# USB_C.net
KiCad netlist of a schematic drawn in Altium Designer
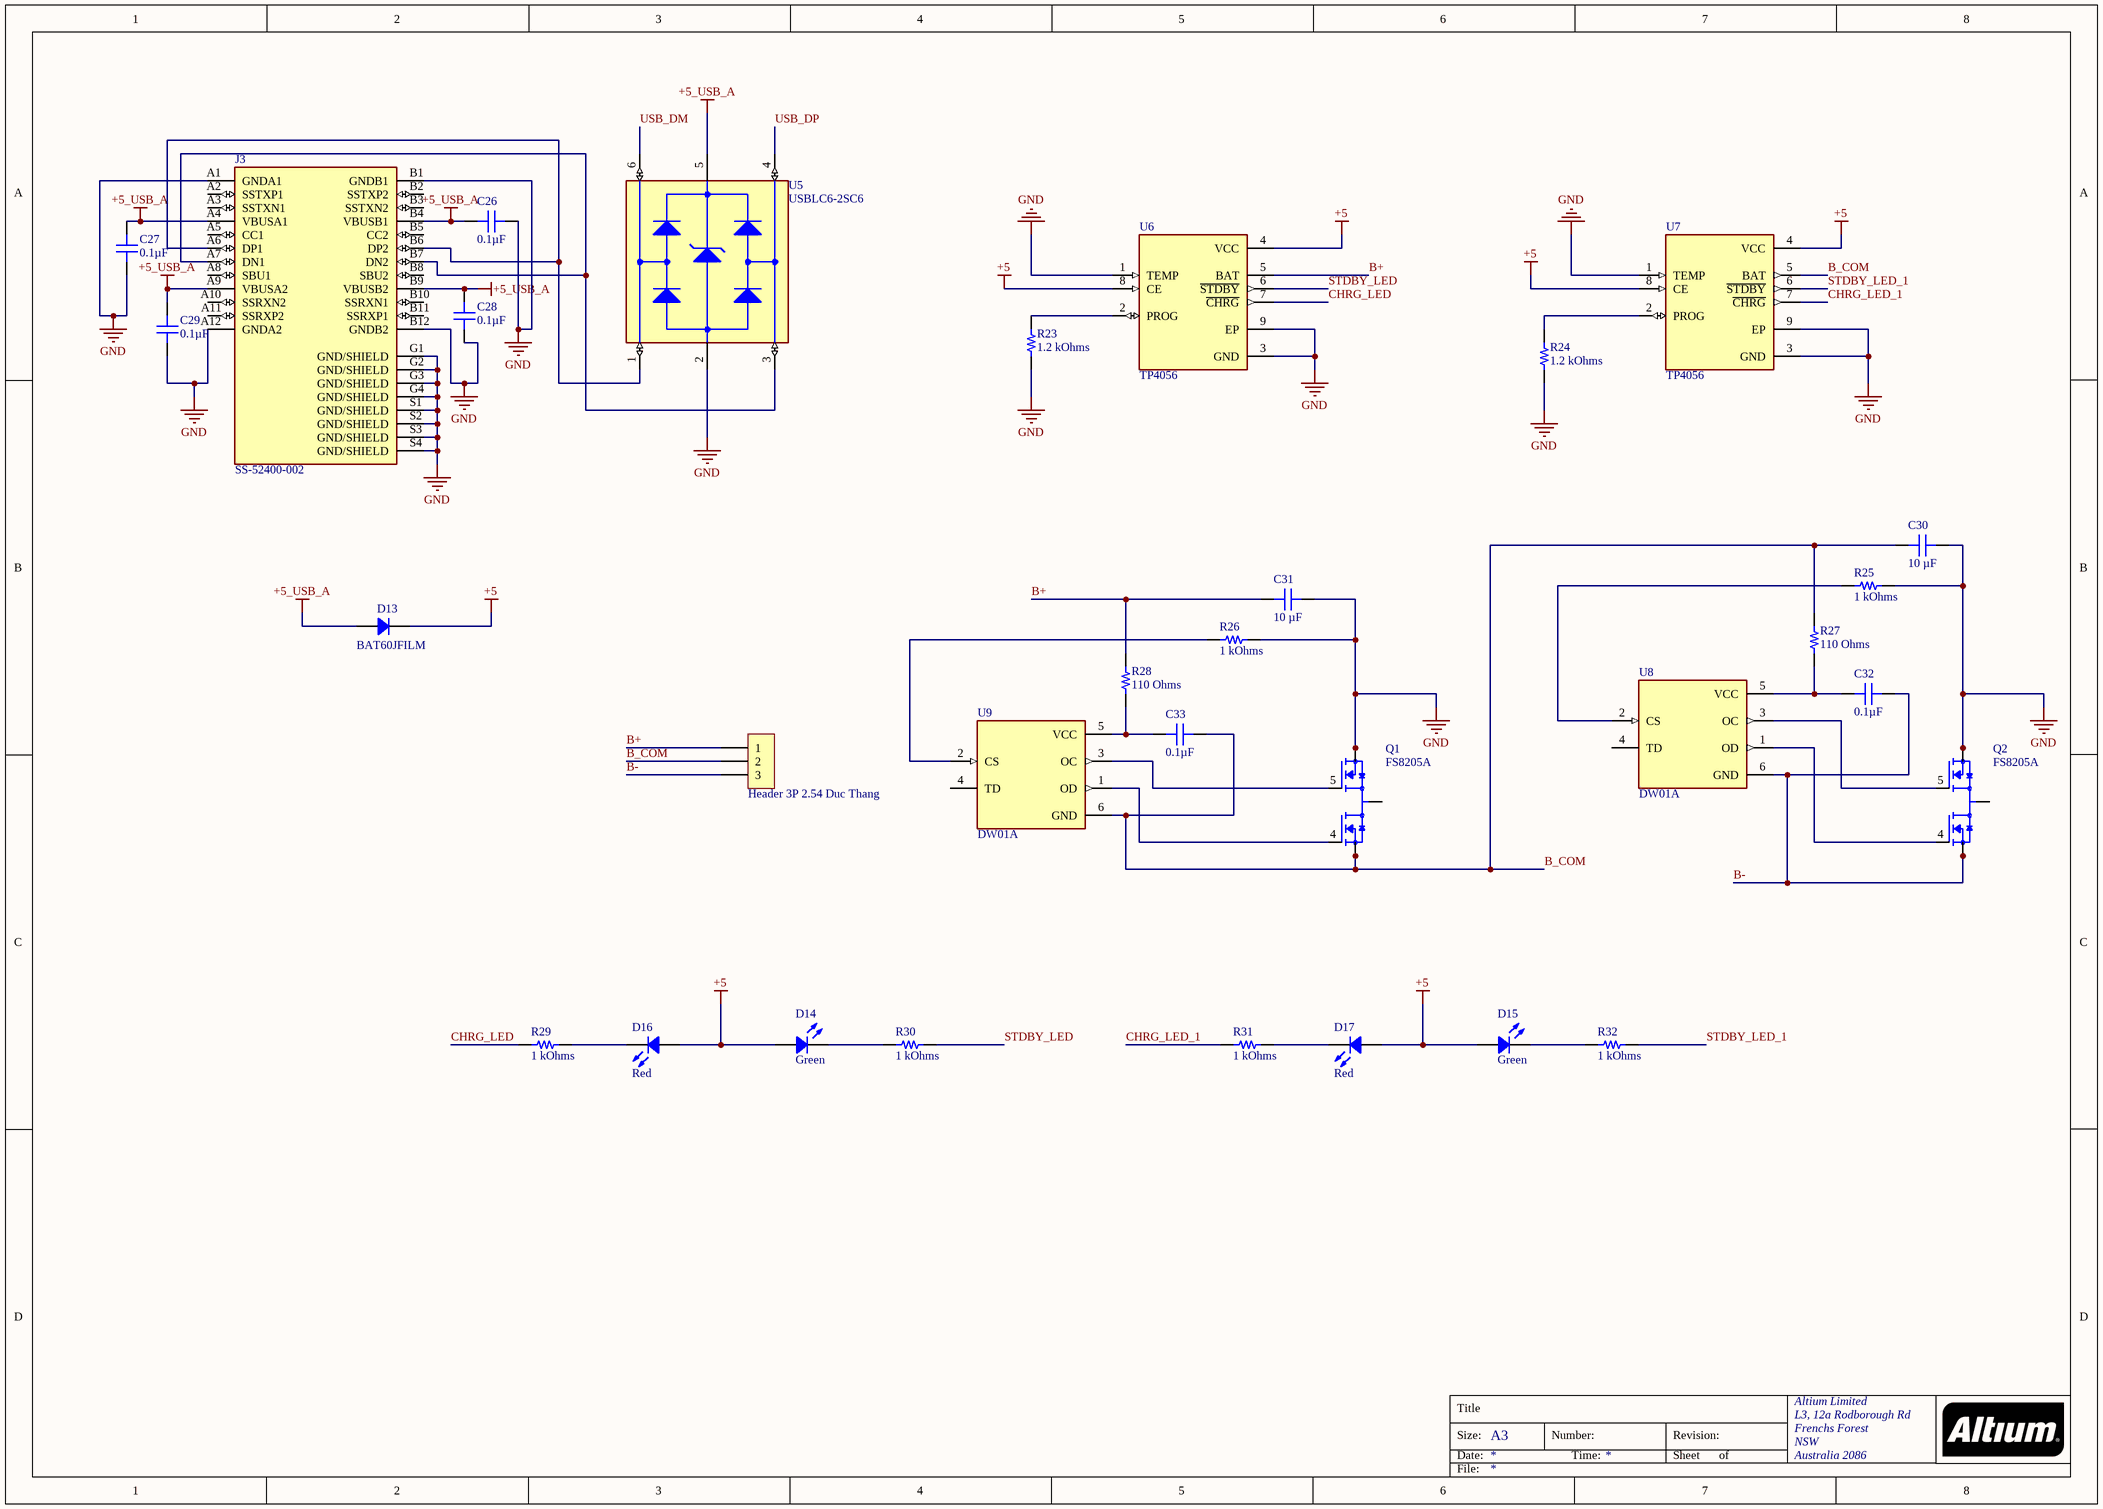
[diagram p0: USB_C.SchDoc]

(export (version "E")
  (design (tool "Eeschema 10.0.6"))
  (components
    (comp (ref "C26")
      (value "0.1µF")
      (footprint "CAP 0603_1608")
      (description "CAP CER 0.1UF 16V X7R 0603")
      (fields (field (name "PART NUMBER") "LD03YC104JAB2A") (field (name "MANUFACTURER") "AVX Corporation"))
      (libsource (lib "Celestial Altium Library - altium_library") (part "Capacitor"))
    )
    (comp (ref "C27")
      (value "0.1µF")
      (footprint "CAP 0603_1608")
      (description "CAP CER 0.1UF 16V X7R 0603")
      (fields (field (name "PART NUMBER") "LD03YC104JAB2A") (field (name "MANUFACTURER") "AVX Corporation"))
      (libsource (lib "Celestial Altium Library - altium_library") (part "Capacitor"))
    )
    (comp (ref "C28")
      (value "0.1µF")
      (footprint "CAP 0603_1608")
      (description "CAP CER 0.1UF 16V X7R 0603")
      (fields (field (name "PART NUMBER") "LD03YC104JAB2A") (field (name "MANUFACTURER") "AVX Corporation"))
      (libsource (lib "Celestial Altium Library - altium_library") (part "Capacitor"))
    )
    (comp (ref "C29")
      (value "0.1µF")
      (footprint "CAP 0603_1608")
      (description "CAP CER 0.1UF 16V X7R 0603")
      (fields (field (name "PART NUMBER") "LD03YC104JAB2A") (field (name "MANUFACTURER") "AVX Corporation"))
      (libsource (lib "Celestial Altium Library - altium_library") (part "Capacitor"))
    )
    (comp (ref "C30")
      (value "10 µF")
      (footprint "CAP 0603_1608")
      (description "CAP CER 10UF 10V X6S 0603")
      (fields
        (field (name "PART NUMBER") "ZRB18AC81A106KE01L")
        (field (name "MANUFACTURER") "Murata Electronics")
      )
      (libsource (lib "Celestial Altium Library - altium_library") (part "Capacitor"))
    )
    (comp (ref "C31")
      (value "10 µF")
      (footprint "CAP 0603_1608")
      (description "CAP CER 10UF 10V X6S 0603")
      (fields
        (field (name "PART NUMBER") "ZRB18AC81A106KE01L")
        (field (name "MANUFACTURER") "Murata Electronics")
      )
      (libsource (lib "Celestial Altium Library - altium_library") (part "Capacitor"))
    )
    (comp (ref "C32")
      (value "0.1µF")
      (footprint "CAP 0603_1608")
      (description "CAP CER 0.1UF 16V X7R 0603")
      (fields (field (name "PART NUMBER") "LD03YC104JAB2A") (field (name "MANUFACTURER") "AVX Corporation"))
      (libsource (lib "Celestial Altium Library - altium_library") (part "Capacitor"))
    )
    (comp (ref "C33")
      (value "0.1µF")
      (footprint "CAP 0603_1608")
      (description "CAP CER 0.1UF 16V X7R 0603")
      (fields (field (name "PART NUMBER") "LD03YC104JAB2A") (field (name "MANUFACTURER") "AVX Corporation"))
      (libsource (lib "Celestial Altium Library - altium_library") (part "Capacitor"))
    )
    (comp (ref "D13")
      (value "BAT60JFILM")
      (footprint "SOD323")
      (description "DIODE SCHOTTKY 10V 3A SOD323")
      (fields (field (name "MANUFACTURER") "STMicroelectronics"))
      (libsource (lib "Celestial Altium Library - altium_library") (part "Diode"))
    )
    (comp (ref "D14")
      (value "Green")
      (footprint "LED 0603_1608 GREEN")
      (description "LED GREEN DIFFUSED 0603 SMD")
      (fields
        (field (name "PART NUMBER") "LT Q39G-Q1OO-25-1")
        (field (name "MANUFACTURER") "OSRAM Opto Semiconductors Inc.")
      )
      (libsource (lib "Celestial Altium Library - altium_library") (part "LED"))
    )
    (comp (ref "D15")
      (value "Green")
      (footprint "LED 0603_1608 GREEN")
      (description "LED GREEN DIFFUSED 0603 SMD")
      (fields
        (field (name "PART NUMBER") "LT Q39G-Q1OO-25-1")
        (field (name "MANUFACTURER") "OSRAM Opto Semiconductors Inc.")
      )
      (libsource (lib "Celestial Altium Library - altium_library") (part "LED"))
    )
    (comp (ref "D16")
      (value "Red")
      (footprint "LED 0603_1608 RED")
      (description "LED RED 0603 SMD")
      (fields (field (name "PART NUMBER") "SML-D13U8WT86") (field (name "MANUFACTURER") "Rohm Semiconductor"))
      (libsource (lib "Celestial Altium Library - altium_library") (part "LED"))
    )
    (comp (ref "D17")
      (value "Red")
      (footprint "LED 0603_1608 RED")
      (description "LED RED 0603 SMD")
      (fields (field (name "PART NUMBER") "SML-D13U8WT86") (field (name "MANUFACTURER") "Rohm Semiconductor"))
      (libsource (lib "Celestial Altium Library - altium_library") (part "LED"))
    )
    (comp (ref "H1")
      (value "Header 3P 2.54 Duc Thang")
      (footprint "XH2.54M-3")
      (description "Cắm")
      (libsource (lib "Header") (part "Header 3P 2.54 Duc Thang"))
    )
    (comp (ref "J3")
      (value "SS-52400-002")
      (footprint "BELFUSE_SS-52400-002")
      (description "USB Type-C Connector ¦ 1 Port ¦ Right Angle Receptacle ¦ Shielded ¦ 0.039[1.00mm]")
      (fields (field (name "MF") "Stewart Connector"))
      (libsource (lib "SS-52400-002") (part "SS-52400-002"))
    )
    (comp (ref "Q1")
      (value "FS8205A")
      (footprint "SOP65P640X120-8N")
      (fields (field (name "MF") "Fortune Semiconductor"))
      (libsource (lib "FS8205A") (part "FS8205A"))
    )
    (comp (ref "Q2")
      (value "FS8205A")
      (footprint "SOP65P640X120-8N")
      (fields (field (name "MF") "Fortune Semiconductor"))
      (libsource (lib "FS8205A") (part "FS8205A"))
    )
    (comp (ref "R23")
      (value "1.2 kOhms")
      (footprint "RES 0402_1005")
      (description "RES SMD 1.2K OHM 1% 1/10W 0402")
      (fields
        (field (name "PART NUMBER") "ERJ-2RKF1201X")
        (field (name "MANUFACTURER") "Panasonic Electronic Components")
      )
      (libsource (lib "Celestial Altium Library - altium_library") (part "Resistor"))
    )
    (comp (ref "R24")
      (value "1.2 kOhms")
      (footprint "RES 0402_1005")
      (description "RES SMD 1.2K OHM 1% 1/10W 0402")
      (fields
        (field (name "PART NUMBER") "MCS04020C1201FE000")
        (field (name "MANUFACTURER") "Vishay Beyschlag")
      )
      (libsource (lib "Celestial Altium Library - altium_library") (part "Resistor"))
    )
    (comp (ref "R25")
      (value "1 kOhms")
      (footprint "RES 0603_1608")
      (description "RES SMD 1K OHM 0.1% 1/10W 0603")
      (fields
        (field (name "PART NUMBER") "M55342E12B1B00RWS")
        (field (name "MANUFACTURER") "Vishay Dale Thin Film")
      )
      (libsource (lib "Celestial Altium Library - altium_library") (part "Resistor"))
    )
    (comp (ref "R26")
      (value "1 kOhms")
      (footprint "RES 0603_1608")
      (description "RES SMD 1K OHM 0.1% 1/10W 0603")
      (fields
        (field (name "PART NUMBER") "M55342E12B1B00RWS")
        (field (name "MANUFACTURER") "Vishay Dale Thin Film")
      )
      (libsource (lib "Celestial Altium Library - altium_library") (part "Resistor"))
    )
    (comp (ref "R27")
      (value "110 Ohms")
      (footprint "RES 0603_1608")
      (description "RES SMD 110 OHM 1% 1/3W 0603")
      (fields
        (field (name "PART NUMBER") "ERJ-PA3F1100V")
        (field (name "MANUFACTURER") "Panasonic Electronic Components")
      )
      (libsource (lib "Celestial Altium Library - altium_library") (part "Resistor"))
    )
    (comp (ref "R28")
      (value "110 Ohms")
      (footprint "RES 0603_1608")
      (description "RES SMD 110 OHM 1% 1/3W 0603")
      (fields
        (field (name "PART NUMBER") "ERJ-PA3F1100V")
        (field (name "MANUFACTURER") "Panasonic Electronic Components")
      )
      (libsource (lib "Celestial Altium Library - altium_library") (part "Resistor"))
    )
    (comp (ref "R29")
      (value "1 kOhms")
      (footprint "RES 0603_1608")
      (description "RES SMD 1K OHM 0.1% 1/10W 0603")
      (fields
        (field (name "PART NUMBER") "M55342E12B1B00RWS")
        (field (name "MANUFACTURER") "Vishay Dale Thin Film")
      )
      (libsource (lib "Celestial Altium Library - altium_library") (part "Resistor"))
    )
    (comp (ref "R30")
      (value "1 kOhms")
      (footprint "RES 0603_1608")
      (description "RES SMD 1K OHM 0.1% 1/10W 0603")
      (fields
        (field (name "PART NUMBER") "M55342E12B1B00RWS")
        (field (name "MANUFACTURER") "Vishay Dale Thin Film")
      )
      (libsource (lib "Celestial Altium Library - altium_library") (part "Resistor"))
    )
    (comp (ref "R31")
      (value "1 kOhms")
      (footprint "RES 0603_1608")
      (description "RES SMD 1K OHM 0.1% 1/10W 0603")
      (fields
        (field (name "PART NUMBER") "M55342E12B1B00RWS")
        (field (name "MANUFACTURER") "Vishay Dale Thin Film")
      )
      (libsource (lib "Celestial Altium Library - altium_library") (part "Resistor"))
    )
    (comp (ref "R32")
      (value "1 kOhms")
      (footprint "RES 0603_1608")
      (description "RES SMD 1K OHM 0.1% 1/10W 0603")
      (fields
        (field (name "PART NUMBER") "M55342E12B1B00RWS")
        (field (name "MANUFACTURER") "Vishay Dale Thin Film")
      )
      (libsource (lib "Celestial Altium Library - altium_library") (part "Resistor"))
    )
    (comp (ref "U5")
      (value "USBLC6-2SC6")
      (footprint "SOT95P280X145-6N")
      (description "17V Clamp 5A (8/20Âµs) Ipp Tvs Diode Surface Mount SOT-23-6")
      (fields (field (name "MF") "STMicroelectronics"))
      (libsource (lib "USBLC6-2SC6") (part "USBLC6-2SC6"))
    )
    (comp (ref "U6")
      (value "TP4056")
      (footprint "SOP127P600X175-9N")
      (description "Complete single cell Li-Ion battery with a constant current / constant voltage linear charger")
      (fields (field (name "MF") "NanJing Top Power ASIC Corp."))
      (libsource (lib "TP4056") (part "TP4056"))
    )
    (comp (ref "U7")
      (value "TP4056")
      (footprint "SOP127P600X175-9N")
      (description "Complete single cell Li-Ion battery with a constant current / constant voltage linear charger")
      (fields (field (name "MF") "NanJing Top Power ASIC Corp."))
      (libsource (lib "TP4056") (part "TP4056"))
    )
    (comp (ref "U8")
      (value "DW01A")
      (footprint "SOT95P280X145-6N")
      (description "One Cell Lithium-ion/Polymer Battery Protection IC")
      (fields (field (name "MF") "Fortune Semiconductor"))
      (libsource (lib "DW01A") (part "DW01A"))
    )
    (comp (ref "U9")
      (value "DW01A")
      (footprint "SOT95P280X145-6N")
      (description "One Cell Lithium-ion/Polymer Battery Protection IC")
      (fields (field (name "MF") "Fortune Semiconductor"))
      (libsource (lib "DW01A") (part "DW01A"))
    )
  )
  (nets
    (net (code "1") (name "+5") (class "Default")
      (node (ref "D13") (pin "2") (pinfunction "2_2") (pintype "passive"))
      (node (ref "D14") (pin "1") (pinfunction "1_1") (pintype "passive"))
      (node (ref "D15") (pin "1") (pinfunction "1_1") (pintype "passive"))
      (node (ref "D16") (pin "1") (pinfunction "1_1") (pintype "passive"))
      (node (ref "D17") (pin "1") (pinfunction "1_1") (pintype "passive"))
      (node (ref "U6") (pin "4") (pinfunction "VCC_4") (pintype "power_in"))
      (node (ref "U6") (pin "8") (pinfunction "CE_8") (pintype "input"))
      (node (ref "U7") (pin "4") (pinfunction "VCC_4") (pintype "power_in"))
      (node (ref "U7") (pin "8") (pinfunction "CE_8") (pintype "input"))
    )
    (net (code "2") (name "+5_USB_A") (class "Default")
      (node (ref "C26") (pin "2") (pinfunction "2_2") (pintype "passive"))
      (node (ref "C27") (pin "2") (pinfunction "2_2") (pintype "passive"))
      (node (ref "C28") (pin "2") (pinfunction "2_2") (pintype "passive"))
      (node (ref "C29") (pin "2") (pinfunction "2_2") (pintype "passive"))
      (node (ref "D13") (pin "1") (pinfunction "1_1") (pintype "passive"))
      (node (ref "J3") (pin "A4") (pinfunction "VBUSA1_A4") (pintype "power_in"))
      (node (ref "J3") (pin "A9") (pinfunction "VBUSA2_A9") (pintype "power_in"))
      (node (ref "J3") (pin "B4") (pinfunction "VBUSB1_B4") (pintype "power_in"))
      (node (ref "J3") (pin "B9") (pinfunction "VBUSB2_B9") (pintype "power_in"))
      (node (ref "U5") (pin "5") (pinfunction "VBUS_5") (pintype "power_in"))
    )
    (net (code "3") (name "/B+") (class "Default")
      (node (ref "C31") (pin "1") (pinfunction "1_1") (pintype "passive"))
      (node (ref "H1") (pin "1") (pinfunction "1_1") (pintype "passive"))
      (node (ref "R28") (pin "2") (pinfunction "2_2") (pintype "passive"))
      (node (ref "U6") (pin "5") (pinfunction "BAT_5") (pintype "power_in"))
    )
    (net (code "4") (name "/B-") (class "Default")
      (node (ref "C32") (pin "1") (pinfunction "1_1") (pintype "passive"))
      (node (ref "H1") (pin "3") (pinfunction "3_3") (pintype "passive"))
      (node (ref "Q2") (pin "2") (pinfunction "S1_2") (pintype "passive"))
      (node (ref "Q2") (pin "3") (pinfunction "S1_3") (pintype "passive"))
      (node (ref "U8") (pin "6") (pinfunction "GND_6") (pintype "power_in"))
    )
    (net (code "5") (name "/B_COM") (class "Default")
      (node (ref "C30") (pin "1") (pinfunction "1_1") (pintype "passive"))
      (node (ref "C33") (pin "1") (pinfunction "1_1") (pintype "passive"))
      (node (ref "H1") (pin "2") (pinfunction "2_2") (pintype "passive"))
      (node (ref "Q1") (pin "2") (pinfunction "S1_2") (pintype "passive"))
      (node (ref "Q1") (pin "3") (pinfunction "S1_3") (pintype "passive"))
      (node (ref "R27") (pin "2") (pinfunction "2_2") (pintype "passive"))
      (node (ref "U7") (pin "5") (pinfunction "BAT_5") (pintype "power_in"))
      (node (ref "U9") (pin "6") (pinfunction "GND_6") (pintype "power_in"))
    )
    (net (code "6") (name "/CHRG_LED") (class "Default")
      (node (ref "R29") (pin "1") (pinfunction "1_1") (pintype "passive"))
      (node (ref "U6") (pin "7") (pinfunction "~{CHRG}_7") (pintype "output"))
    )
    (net (code "7") (name "/CHRG_LED_1") (class "Default")
      (node (ref "R31") (pin "1") (pinfunction "1_1") (pintype "passive"))
      (node (ref "U7") (pin "7") (pinfunction "~{CHRG}_7") (pintype "output"))
    )
    (net (code "8") (name "/STDBY_LED") (class "Default")
      (node (ref "R30") (pin "2") (pinfunction "2_2") (pintype "passive"))
      (node (ref "U6") (pin "6") (pinfunction "~{STDBY}_6") (pintype "output"))
    )
    (net (code "9") (name "/STDBY_LED_1") (class "Default")
      (node (ref "R32") (pin "2") (pinfunction "2_2") (pintype "passive"))
      (node (ref "U7") (pin "6") (pinfunction "~{STDBY}_6") (pintype "output"))
    )
    (net (code "10") (name "/USB_DM") (class "Default")
      (node (ref "U5") (pin "6") (pinfunction "I/O1_OUT_6") (pintype "bidirectional"))
    )
    (net (code "11") (name "/USB_DP") (class "Default")
      (node (ref "U5") (pin "4") (pinfunction "I/O2_OUT_4") (pintype "bidirectional"))
    )
    (net (code "12") (name "GND") (class "Default")
      (node (ref "C26") (pin "1") (pinfunction "1_1") (pintype "passive"))
      (node (ref "C27") (pin "1") (pinfunction "1_1") (pintype "passive"))
      (node (ref "C28") (pin "1") (pinfunction "1_1") (pintype "passive"))
      (node (ref "C29") (pin "1") (pinfunction "1_1") (pintype "passive"))
      (node (ref "C30") (pin "2") (pinfunction "2_2") (pintype "passive"))
      (node (ref "C31") (pin "2") (pinfunction "2_2") (pintype "passive"))
      (node (ref "J3") (pin "A1") (pinfunction "GNDA1_A1") (pintype "power_in"))
      (node (ref "J3") (pin "A12") (pinfunction "GNDA2_A12") (pintype "power_in"))
      (node (ref "J3") (pin "B1") (pinfunction "GNDB1_B1") (pintype "power_in"))
      (node (ref "J3") (pin "B12") (pinfunction "GNDB2_B12") (pintype "power_in"))
      (node (ref "J3") (pin "G1") (pinfunction "GND/SHIELD_G1") (pintype "power_in"))
      (node (ref "J3") (pin "G2") (pinfunction "GND/SHIELD_G2") (pintype "power_in"))
      (node (ref "J3") (pin "G3") (pinfunction "GND/SHIELD_G3") (pintype "power_in"))
      (node (ref "J3") (pin "G4") (pinfunction "GND/SHIELD_G4") (pintype "power_in"))
      (node (ref "J3") (pin "S1") (pinfunction "GND/SHIELD_S1") (pintype "power_in"))
      (node (ref "J3") (pin "S2") (pinfunction "GND/SHIELD_S2") (pintype "power_in"))
      (node (ref "J3") (pin "S3") (pinfunction "GND/SHIELD_S3") (pintype "power_in"))
      (node (ref "J3") (pin "S4") (pinfunction "GND/SHIELD_S4") (pintype "power_in"))
      (node (ref "Q1") (pin "6") (pinfunction "S2_6") (pintype "passive"))
      (node (ref "Q1") (pin "7") (pinfunction "S2_7") (pintype "passive"))
      (node (ref "Q2") (pin "6") (pinfunction "S2_6") (pintype "passive"))
      (node (ref "Q2") (pin "7") (pinfunction "S2_7") (pintype "passive"))
      (node (ref "R23") (pin "1") (pinfunction "1_1") (pintype "passive"))
      (node (ref "R24") (pin "1") (pinfunction "1_1") (pintype "passive"))
      (node (ref "R25") (pin "2") (pinfunction "2_2") (pintype "passive"))
      (node (ref "R26") (pin "2") (pinfunction "2_2") (pintype "passive"))
      (node (ref "U5") (pin "2") (pinfunction "GND_2") (pintype "power_in"))
      (node (ref "U6") (pin "1") (pinfunction "TEMP_1") (pintype "input"))
      (node (ref "U6") (pin "3") (pinfunction "GND_3") (pintype "power_in"))
      (node (ref "U6") (pin "9") (pinfunction "EP_9") (pintype "passive"))
      (node (ref "U7") (pin "1") (pinfunction "TEMP_1") (pintype "input"))
      (node (ref "U7") (pin "3") (pinfunction "GND_3") (pintype "power_in"))
      (node (ref "U7") (pin "9") (pinfunction "EP_9") (pintype "passive"))
    )
    (net (code "13") (name "Net-(D14-Pad2)") (class "Default")
      (node (ref "D14") (pin "2") (pinfunction "2_2") (pintype "passive"))
      (node (ref "R30") (pin "1") (pinfunction "1_1") (pintype "passive"))
    )
    (net (code "14") (name "Net-(D15-Pad2)") (class "Default")
      (node (ref "D15") (pin "2") (pinfunction "2_2") (pintype "passive"))
      (node (ref "R32") (pin "1") (pinfunction "1_1") (pintype "passive"))
    )
    (net (code "15") (name "Net-(D16-Pad2)") (class "Default")
      (node (ref "D16") (pin "2") (pinfunction "2_2") (pintype "passive"))
      (node (ref "R29") (pin "2") (pinfunction "2_2") (pintype "passive"))
    )
    (net (code "16") (name "Net-(D17-Pad2)") (class "Default")
      (node (ref "D17") (pin "2") (pinfunction "2_2") (pintype "passive"))
      (node (ref "R31") (pin "2") (pinfunction "2_2") (pintype "passive"))
    )
    (net (code "17") (name "Net-(J3-DN1)") (class "Default")
      (node (ref "J3") (pin "A7") (pinfunction "DN1_A7") (pintype "bidirectional"))
      (node (ref "J3") (pin "B7") (pinfunction "DN2_B7") (pintype "bidirectional"))
      (node (ref "U5") (pin "3") (pinfunction "I/O2_IN_3") (pintype "bidirectional"))
    )
    (net (code "18") (name "Net-(J3-DP1)") (class "Default")
      (node (ref "J3") (pin "A6") (pinfunction "DP1_A6") (pintype "bidirectional"))
      (node (ref "J3") (pin "B6") (pinfunction "DP2_B6") (pintype "bidirectional"))
      (node (ref "U5") (pin "1") (pinfunction "I/O1_IN_1") (pintype "bidirectional"))
    )
    (net (code "19") (name "Net-(Q1-D12-Pad1)") (class "Default")
      (node (ref "Q1") (pin "1") (pinfunction "D12_1") (pintype "passive"))
      (node (ref "Q1") (pin "8") (pinfunction "D12_8") (pintype "passive"))
    )
    (net (code "20") (name "Net-(Q1-G1)") (class "Default")
      (node (ref "Q1") (pin "4") (pinfunction "G1_4") (pintype "passive"))
      (node (ref "U9") (pin "1") (pinfunction "OD_1") (pintype "output"))
    )
    (net (code "21") (name "Net-(Q1-G2)") (class "Default")
      (node (ref "Q1") (pin "5") (pinfunction "G2_5") (pintype "passive"))
      (node (ref "U9") (pin "3") (pinfunction "OC_3") (pintype "output"))
    )
    (net (code "22") (name "Net-(Q2-D12-Pad1)") (class "Default")
      (node (ref "Q2") (pin "1") (pinfunction "D12_1") (pintype "passive"))
      (node (ref "Q2") (pin "8") (pinfunction "D12_8") (pintype "passive"))
    )
    (net (code "23") (name "Net-(Q2-G1)") (class "Default")
      (node (ref "Q2") (pin "4") (pinfunction "G1_4") (pintype "passive"))
      (node (ref "U8") (pin "1") (pinfunction "OD_1") (pintype "output"))
    )
    (net (code "24") (name "Net-(Q2-G2)") (class "Default")
      (node (ref "Q2") (pin "5") (pinfunction "G2_5") (pintype "passive"))
      (node (ref "U8") (pin "3") (pinfunction "OC_3") (pintype "output"))
    )
    (net (code "25") (name "Net-(U6-PROG)") (class "Default")
      (node (ref "R23") (pin "2") (pinfunction "2_2") (pintype "passive"))
      (node (ref "U6") (pin "2") (pinfunction "PROG_2") (pintype "bidirectional"))
    )
    (net (code "26") (name "Net-(U7-PROG)") (class "Default")
      (node (ref "R24") (pin "2") (pinfunction "2_2") (pintype "passive"))
      (node (ref "U7") (pin "2") (pinfunction "PROG_2") (pintype "bidirectional"))
    )
    (net (code "27") (name "Net-(U8-CS)") (class "Default")
      (node (ref "R25") (pin "1") (pinfunction "1_1") (pintype "passive"))
      (node (ref "U8") (pin "2") (pinfunction "CS_2") (pintype "input"))
    )
    (net (code "28") (name "Net-(U8-VCC)") (class "Default")
      (node (ref "C32") (pin "2") (pinfunction "2_2") (pintype "passive"))
      (node (ref "R27") (pin "1") (pinfunction "1_1") (pintype "passive"))
      (node (ref "U8") (pin "5") (pinfunction "VCC_5") (pintype "power_in"))
    )
    (net (code "29") (name "Net-(U9-CS)") (class "Default")
      (node (ref "R26") (pin "1") (pinfunction "1_1") (pintype "passive"))
      (node (ref "U9") (pin "2") (pinfunction "CS_2") (pintype "input"))
    )
    (net (code "30") (name "Net-(U9-VCC)") (class "Default")
      (node (ref "C33") (pin "2") (pinfunction "2_2") (pintype "passive"))
      (node (ref "R28") (pin "1") (pinfunction "1_1") (pintype "passive"))
      (node (ref "U9") (pin "5") (pinfunction "VCC_5") (pintype "power_in"))
    )
    (net (code "31") (name "unconnected-(J3-CC1-PadA5)") (class "Default")
      (node (ref "J3") (pin "A5") (pinfunction "CC1_A5") (pintype "bidirectional"))
    )
    (net (code "32") (name "unconnected-(J3-CC2-PadB5)") (class "Default")
      (node (ref "J3") (pin "B5") (pinfunction "CC2_B5") (pintype "bidirectional"))
    )
    (net (code "33") (name "unconnected-(J3-SBU1-PadA8)") (class "Default")
      (node (ref "J3") (pin "A8") (pinfunction "SBU1_A8") (pintype "bidirectional"))
    )
    (net (code "34") (name "unconnected-(J3-SBU2-PadB8)") (class "Default")
      (node (ref "J3") (pin "B8") (pinfunction "SBU2_B8") (pintype "bidirectional"))
    )
    (net (code "35") (name "unconnected-(J3-SSRXN1-PadB10)") (class "Default")
      (node (ref "J3") (pin "B10") (pinfunction "SSRXN1_B10") (pintype "bidirectional"))
    )
    (net (code "36") (name "unconnected-(J3-SSRXN2-PadA10)") (class "Default")
      (node (ref "J3") (pin "A10") (pinfunction "SSRXN2_A10") (pintype "bidirectional"))
    )
    (net (code "37") (name "unconnected-(J3-SSRXP1-PadB11)") (class "Default")
      (node (ref "J3") (pin "B11") (pinfunction "SSRXP1_B11") (pintype "bidirectional"))
    )
    (net (code "38") (name "unconnected-(J3-SSRXP2-PadA11)") (class "Default")
      (node (ref "J3") (pin "A11") (pinfunction "SSRXP2_A11") (pintype "bidirectional"))
    )
    (net (code "39") (name "unconnected-(J3-SSTXN1-PadA3)") (class "Default")
      (node (ref "J3") (pin "A3") (pinfunction "SSTXN1_A3") (pintype "bidirectional"))
    )
    (net (code "40") (name "unconnected-(J3-SSTXN2-PadB3)") (class "Default")
      (node (ref "J3") (pin "B3") (pinfunction "SSTXN2_B3") (pintype "bidirectional"))
    )
    (net (code "41") (name "unconnected-(J3-SSTXP1-PadA2)") (class "Default")
      (node (ref "J3") (pin "A2") (pinfunction "SSTXP1_A2") (pintype "bidirectional"))
    )
    (net (code "42") (name "unconnected-(J3-SSTXP2-PadB2)") (class "Default")
      (node (ref "J3") (pin "B2") (pinfunction "SSTXP2_B2") (pintype "bidirectional"))
    )
    (net (code "43") (name "unconnected-(U8-TD-Pad4)") (class "Default")
      (node (ref "U8") (pin "4") (pinfunction "TD_4") (pintype "passive"))
    )
    (net (code "44") (name "unconnected-(U9-TD-Pad4)") (class "Default")
      (node (ref "U9") (pin "4") (pinfunction "TD_4") (pintype "passive"))
    )
  )
)
